# 05_-_POWER.net
KiCad netlist of a schematic drawn in Altium Designer
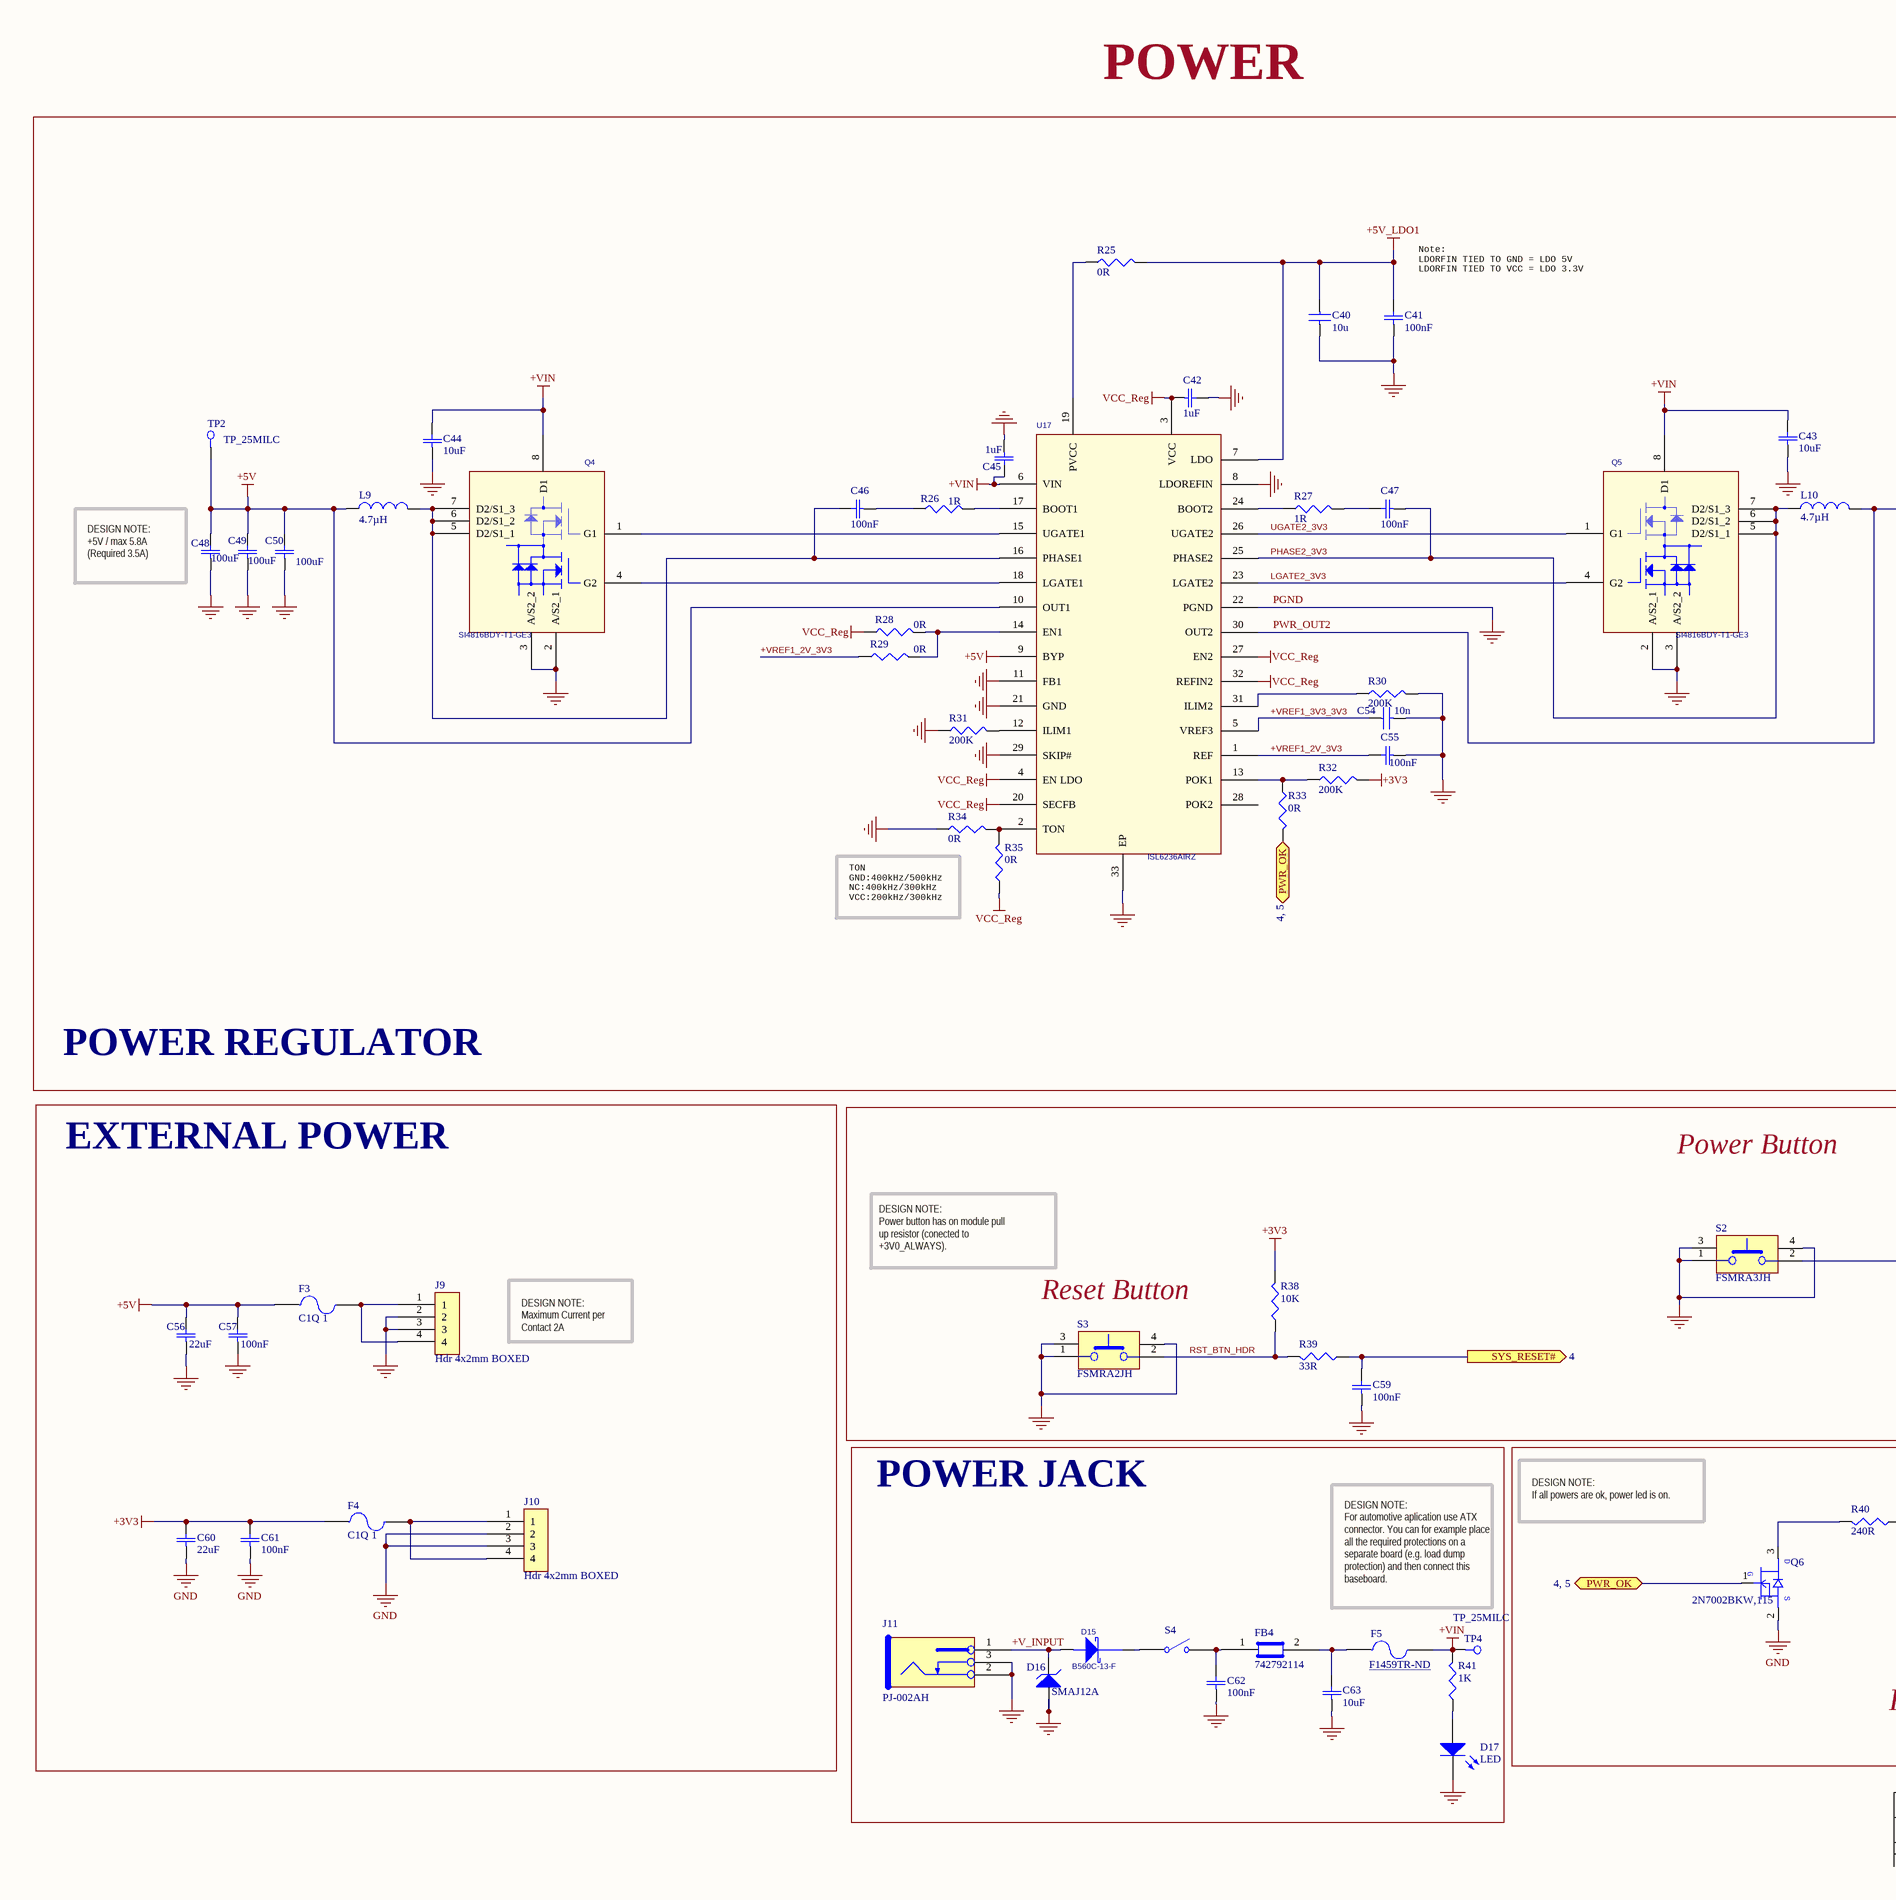
[diagram p0: [05] - POWER.SchDoc, left]
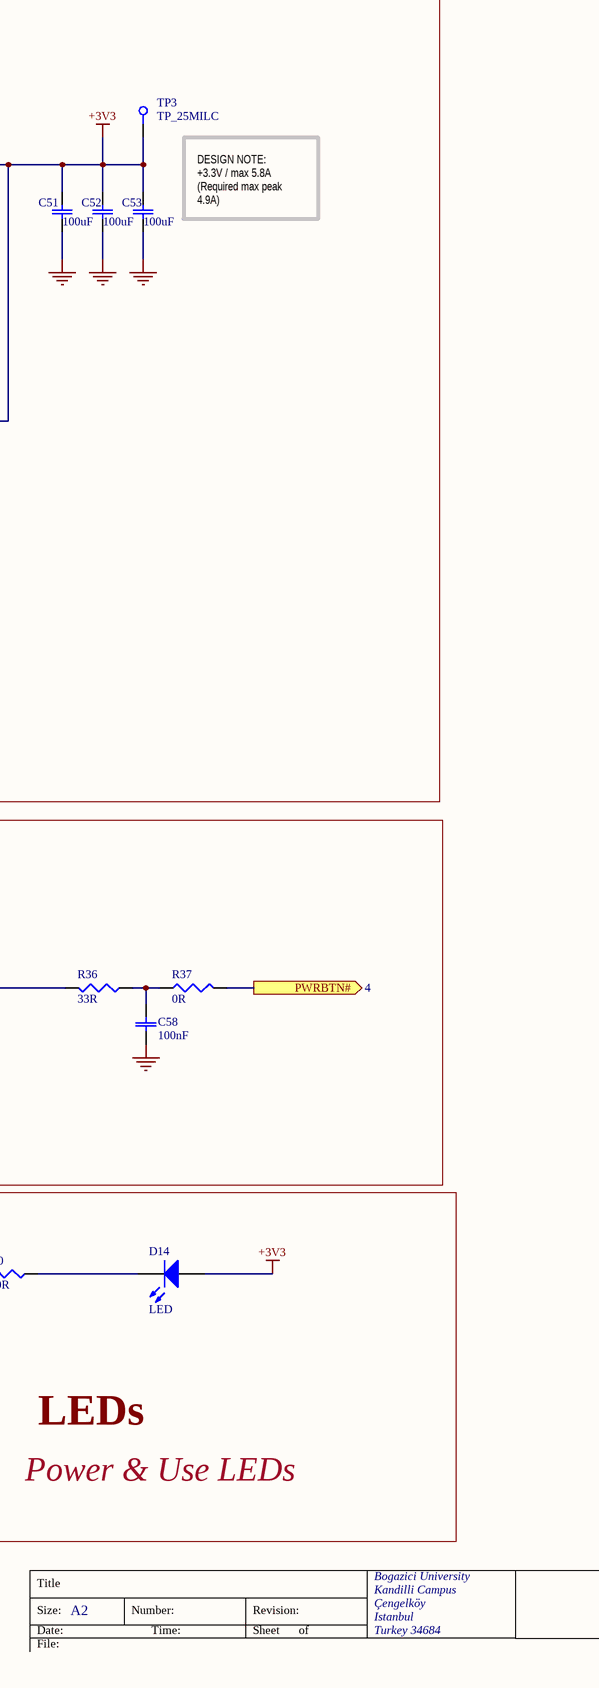
[diagram p1: [05] - POWER.SchDoc, right]

(export (version "E")
  (design (tool "Eeschema 10.0.6"))
  (components
    (comp (ref "C40")
      (value "10u")
      (footprint "iMX6 Rex Development Baseboard V1I1_PCB:C0603")
      (description "CAP CER 10UF 6.3V X5R 20% 0603")
      (fields
        (field (name "MANUFACTURER") "TDK Corporation")
        (field (name "MANUFACTURER PART NUMBER") "C1608X5R0J106M")
      )
      (libsource (lib "SYNCBOX_V3I1") (part "C1608X5R0J106M"))
    )
    (comp (ref "C41")
      (value "100nF")
      (footprint "C0402")
      (description "CAP CER 0.1UF 50V X8R 0603")
      (fields (field (name "TOLERANCE") "±10%"))
      (libsource (lib "SYNCBOX_V3I1") (part "CL05A104KA5NNNC"))
    )
    (comp (ref "C42")
      (value "1uF")
      (footprint "CAP_3216")
      (description "CAP CER 1UF 50V X8R 1206")
      (fields
        (field (name "MANUFACTURER_PART_NUMBER") "CGA5L3X8R1H105K160AB")
        (field (name "TOLERANCE") "±10%")
      )
      (libsource (lib "SYNCBOX_V3I1") (part "CGA5L3X8R1H105K1"))
    )
    (comp (ref "C43")
      (value "10uF")
      (footprint "CAP_3216")
      (description "CAP CER 10UF 35V JB 1206")
      (fields
        (field (name "TOLERANCE") "±10%")
        (field (name "MANUFACTURER_PART_NUMBER") "C3216JB1V106K160AB")
      )
      (libsource (lib "SYNCBOX_V3I1") (part "C3216JB1V106K160"))
    )
    (comp (ref "C44")
      (value "10uF")
      (footprint "CAP_3216")
      (description "CAP CER 10UF 35V JB 1206")
      (fields
        (field (name "TOLERANCE") "±10%")
        (field (name "MANUFACTURER_PART_NUMBER") "C3216JB1V106K160AB")
      )
      (libsource (lib "SYNCBOX_V3I1") (part "C3216JB1V106K160"))
    )
    (comp (ref "C45")
      (value "1uF")
      (footprint "CAP_3216")
      (description "CAP CER 1UF 50V X8R 1206")
      (fields
        (field (name "TOLERANCE") "±10%")
        (field (name "MANUFACTURER_PART_NUMBER") "CGA5L3X8R1H105K160AB")
      )
      (libsource (lib "SYNCBOX_V3I1") (part "CGA5L3X8R1H105K1"))
    )
    (comp (ref "C46")
      (value "100nF")
      (footprint "C0402")
      (description "CAP CER 0.1UF 50V X8R 0603")
      (fields (field (name "TOLERANCE") "±10%"))
      (libsource (lib "SYNCBOX_V3I1") (part "CL05A104KA5NNNC"))
    )
    (comp (ref "C47")
      (value "100nF")
      (footprint "C0402")
      (description "CAP CER 0.1UF 50V X8R 0603")
      (fields (field (name "TOLERANCE") "±10%"))
      (libsource (lib "SYNCBOX_V3I1") (part "CL05A104KA5NNNC"))
    )
    (comp (ref "C48")
      (value "100uF")
      (footprint "C1210C")
      (description "CAP CER 100UF 10V X5R 1210")
      (fields (field (name "TOLERANCE") "±20%") (field (name "MANUFACTURER_PART_NUMBER") "C1210C107M8PACTU"))
      (libsource (lib "SYNCBOX_V3I1") (part "CL32A107MPVNNNE"))
    )
    (comp (ref "C49")
      (value "100uF")
      (footprint "C1210C")
      (description "CAP CER 100UF 10V X5R 1210")
      (fields (field (name "TOLERANCE") "±20%") (field (name "MANUFACTURER_PART_NUMBER") "C1210C107M8PACTU"))
      (libsource (lib "SYNCBOX_V3I1") (part "CL32A107MPVNNNE"))
    )
    (comp (ref "C50")
      (value "100uF")
      (footprint "C1210C")
      (description "CAP CER 100UF 10V X5R 1210")
      (fields (field (name "TOLERANCE") "±20%") (field (name "MANUFACTURER_PART_NUMBER") "C1210C107M8PACTU"))
      (libsource (lib "SYNCBOX_V3I1") (part "CL32A107MPVNNNE"))
    )
    (comp (ref "C51")
      (value "100uF")
      (footprint "C1210C")
      (description "CAP CER 100UF 10V X5R 1210")
      (fields (field (name "TOLERANCE") "±20%") (field (name "MANUFACTURER_PART_NUMBER") "C1210C107M8PACTU"))
      (libsource (lib "SYNCBOX_V3I1") (part "CL32A107MPVNNNE"))
    )
    (comp (ref "C52")
      (value "100uF")
      (footprint "C1210C")
      (description "CAP CER 100UF 10V X5R 1210")
      (fields (field (name "TOLERANCE") "±20%") (field (name "MANUFACTURER_PART_NUMBER") "C1210C107M8PACTU"))
      (libsource (lib "SYNCBOX_V3I1") (part "CL32A107MPVNNNE"))
    )
    (comp (ref "C53")
      (value "100uF")
      (footprint "C1210C")
      (description "CAP CER 100UF 10V X5R 1210")
      (fields (field (name "TOLERANCE") "±20%") (field (name "MANUFACTURER_PART_NUMBER") "C1210C107M8PACTU"))
      (libsource (lib "SYNCBOX_V3I1") (part "CL32A107MPVNNNE"))
    )
    (comp (ref "C54")
      (value "10n")
      (footprint "C0402")
      (description "CAP CER 10000PF 16V X7R 10% 0402")
      (fields
        (field (name "MANUFACTURER") "TDK Corporation")
        (field (name "MANUFACTURER PART NUMBER") "C1005X7R1C103K")
      )
      (libsource (lib "SYNCBOX_V3I1") (part "C1005X7R1C103K"))
    )
    (comp (ref "C55")
      (value "100nF")
      (footprint "C0402")
      (description "CAP CER 0.1UF 50V X8R 0603")
      (fields (field (name "TOLERANCE") "±10%"))
      (libsource (lib "SYNCBOX_V3I1") (part "CL05A104KA5NNNC"))
    )
    (comp (ref "C56")
      (value "22uF")
      (footprint "C0805")
      (description "CAP CER 22UF 16V X5R 0805")
      (fields (field (name "TOLERANCE") "±20%"))
      (libsource (lib "SYNCBOX_V3I1") (part "CL21A226MOCLRNC"))
    )
    (comp (ref "C57")
      (value "100nF")
      (footprint "C0402")
      (description "CAP CER 0.1UF 50V X8R 0603")
      (fields (field (name "TOLERANCE") "±10%"))
      (libsource (lib "SYNCBOX_V3I1") (part "CL05A104KA5NNNC"))
    )
    (comp (ref "C58")
      (value "100nF")
      (footprint "C0402")
      (description "CAP CER 0.1UF 50V X8R 0603")
      (fields (field (name "TOLERANCE") "±10%"))
      (libsource (lib "SYNCBOX_V3I1") (part "CL05A104KA5NNNC"))
    )
    (comp (ref "C59")
      (value "100nF")
      (footprint "C0402")
      (description "CAP CER 0.1UF 50V X8R 0603")
      (fields (field (name "TOLERANCE") "±10%"))
      (libsource (lib "SYNCBOX_V3I1") (part "CL05A104KA5NNNC"))
    )
    (comp (ref "C60")
      (value "22uF")
      (footprint "C0805")
      (description "CAP CER 22UF 16V X5R 0805")
      (fields (field (name "TOLERANCE") "±20%"))
      (libsource (lib "SYNCBOX_V3I1") (part "CL21A226MOCLRNC"))
    )
    (comp (ref "C61")
      (value "100nF")
      (footprint "C0402")
      (description "CAP CER 0.1UF 50V X8R 0603")
      (fields (field (name "TOLERANCE") "±10%"))
      (libsource (lib "SYNCBOX_V3I1") (part "CL05A104KA5NNNC"))
    )
    (comp (ref "C62")
      (value "100nF")
      (footprint "C0402")
      (description "CAP CER 0.1UF 50V X8R 0603")
      (fields (field (name "TOLERANCE") "±10%"))
      (libsource (lib "SYNCBOX_V3I1") (part "CL05A104KA5NNNC"))
    )
    (comp (ref "C63")
      (value "10uF")
      (footprint "CAP_3216")
      (description "CAP CER 10UF 35V JB 1206")
      (fields
        (field (name "TOLERANCE") "±10%")
        (field (name "MANUFACTURER_PART_NUMBER") "C3216JB1V106K160AB")
      )
      (libsource (lib "SYNCBOX_V3I1") (part "C3216JB1V106K160"))
    )
    (comp (ref "D14")
      (value "LED")
      (footprint "D0603_Directional")
      (description "LED COOL WHITE DIFFUSED 0603 SMD")
      (libsource (lib "SYNCBOX_V3I1") (part "LW Q38E-Q1OO-3K6L-1"))
    )
    (comp (ref "D15")
      (value "B560C-13-F")
      (footprint "SYNCBOX_V3I1:SMC")
      (description "DIODE SCHOTTKY 60V 5A SMC")
      (fields (field (name "MANUFACTURER") "Diodes Inc"))
      (libsource (lib "SYNCBOX_V3I1") (part "B560C-13-F"))
    )
    (comp (ref "D16")
      (value "SMAJ12A")
      (footprint "SMA / DO-214AC")
      (description "TVS DIODE 12V 19.9V SMA")
      (fields (field (name "PUBLISHER") "Altium Limited"))
      (libsource (lib "SYNCBOX_V3I1") (part "SMAJ12A"))
    )
    (comp (ref "D17")
      (value "LED")
      (footprint "D0603_Directional")
      (description "LED COOL WHITE DIFFUSED 0603 SMD")
      (libsource (lib "SYNCBOX_V3I1") (part "LW Q38E-Q1OO-3K6L-1"))
    )
    (comp (ref "F3")
      (value "C1Q 1")
      (footprint "C1")
      (description "FUSE BOARD MOUNT 1A 125VAC 63VDC")
      (libsource (lib "SYNCBOX_V3I1") (part "C1Q 1"))
    )
    (comp (ref "F4")
      (value "C1Q 1")
      (footprint "C1")
      (description "FUSE BOARD MOUNT 1A 125VAC 63VDC")
      (libsource (lib "SYNCBOX_V3I1") (part "C1Q 1"))
    )
    (comp (ref "F5")
      (value "F1459TR-ND")
      (footprint "0466Series")
      (description "FUSE BOARD MNT 4A 32VAC/VDC 1206")
      (libsource (lib "SYNCBOX_V3I1") (part "0466004.NR"))
    )
    (comp (ref "FB4")
      (value "742792114")
      (footprint "Ferrite bead")
      (description "FERRITE BEAD 50 OHM 1206 1LN")
      (libsource (lib "SYNCBOX_V3I1") (part "FB742792114"))
    )
    (comp (ref "J9")
      (value "Hdr 4x2mm BOXED")
      (footprint "HDR_1x4_2MM_SHDR")
      (description "CONN HEADER 4POS 2MM VERT TIN")
      (fields
        (field (name "MANUFACTURER") "Molex Inc")
        (field (name "MANUFACTURER PART NUMBER") "0532530470")
        (field (name ".CREATOR") "MM")
      )
      (libsource (lib "SYNCBOX_V3I1") (part "0532530470"))
    )
    (comp (ref "J10")
      (value "Hdr 4x2mm BOXED")
      (footprint "HDR_1x4_2MM_SHDR")
      (description "CONN HEADER 4POS 2MM VERT TIN")
      (fields
        (field (name "MANUFACTURER") "Molex Inc")
        (field (name "MANUFACTURER PART NUMBER") "0532530470")
        (field (name ".CREATOR") "MM")
      )
      (libsource (lib "SYNCBOX_V3I1") (part "0532530470"))
    )
    (comp (ref "J11")
      (value "PJ-002AH")
      (footprint "POWER_JACK_5.5_2.1MM_NS")
      (description "CONN PWR JACK 2.1X5.5MM HIGH CUR")
      (fields (field (name "MANUFACTURER") "CUI Inc"))
      (libsource (lib "SYNCBOX_V3I1") (part "PJ-002AH"))
    )
    (comp (ref "L9")
      (value "4.7µH")
      (footprint "IHLP_255MILx270MIL")
      (description "INDUCTOR POWER 4.7UH 5.5A SMD")
      (fields
        (field (name "MANUFACTURER") "Vishay/Dale")
        (field (name "MANUFACTURER PART NUMBER") "IHLP2525CZER4R7M01")
      )
      (libsource (lib "SYNCBOX_V3I1") (part "IHLP2525CZER4R7M01"))
    )
    (comp (ref "L10")
      (value "4.7µH")
      (footprint "IHLP_255MILx270MIL")
      (description "INDUCTOR POWER 4.7UH 5.5A SMD")
      (fields
        (field (name "MANUFACTURER") "Vishay/Dale")
        (field (name "MANUFACTURER PART NUMBER") "IHLP2525CZER4R7M01")
      )
      (libsource (lib "SYNCBOX_V3I1") (part "IHLP2525CZER4R7M01"))
    )
    (comp (ref "Q4")
      (value "SI4816BDY-T1-GE3")
      (footprint "8_SOIC_3.9MM")
      (description "MOSFET DL N-CH 30V 6.8A 8-SOIC")
      (fields (field (name "MANUFACTURER") "Vishay/Siliconix"))
      (libsource (lib "SYNCBOX_V3I1") (part "SI4816BDY-T1-GE3"))
    )
    (comp (ref "Q5")
      (value "SI4816BDY-T1-GE3")
      (footprint "8_SOIC_3.9MM")
      (description "MOSFET DL N-CH 30V 6.8A 8-SOIC")
      (fields (field (name "MANUFACTURER") "Vishay/Siliconix"))
      (libsource (lib "SYNCBOX_V3I1") (part "SI4816BDY-T1-GE3"))
    )
    (comp (ref "Q6")
      (value "2N7002BKW,115")
      (footprint "SC70_SOT323")
      (description "MOSFET N-CH 60V 310MA SOT323")
      (fields (field (name "MANUFACTURER") "NXP Semiconductors"))
      (libsource (lib "SYNCBOX_V3I1") (part "2N7002BKW,115"))
    )
    (comp (ref "R25")
      (value "0R")
      (footprint "R0402")
      (description "RES SMD 0 OHM JUMPER 1/16W 0402")
      (fields (field (name "TOLERANCE") "Jumper"))
      (libsource (lib "SYNCBOX_V3I1") (part "RC1005J000CS"))
    )
    (comp (ref "R26")
      (value "1R")
      (footprint "R0402")
      (description "RES 1.00 OHM 1/16W 1% 0402 SM")
      (fields
        (field (name "MANUFACTURER") "Yageo")
        (field (name "MANUFACTURER PART NUMBER") "RC0402FR-071RL")
      )
      (libsource (lib "SYNCBOX_V3I1") (part "RC0402FR-071RL"))
    )
    (comp (ref "R27")
      (value "1R")
      (footprint "R0402")
      (description "RES 1.00 OHM 1/16W 1% 0402 SM")
      (fields
        (field (name "MANUFACTURER") "Yageo")
        (field (name "MANUFACTURER PART NUMBER") "RC0402FR-071RL")
      )
      (libsource (lib "SYNCBOX_V3I1") (part "RC0402FR-071RL"))
    )
    (comp (ref "R28")
      (value "0R")
      (footprint "R0402")
      (description "RES SMD 0 OHM JUMPER 1/16W 0402")
      (fields (field (name "TOLERANCE") "Jumper"))
      (libsource (lib "SYNCBOX_V3I1") (part "RC1005J000CS"))
    )
    (comp (ref "R29")
      (value "0R")
      (footprint "R0402")
      (description "RES SMD 0 OHM JUMPER 1/16W 0402")
      (fields (field (name "TOLERANCE") "Jumper"))
      (libsource (lib "SYNCBOX_V3I1") (part "RC1005J000CS"))
    )
    (comp (ref "R30")
      (value "200K")
      (footprint "R0402")
      (description "RES SMD 200K OHM 1% 1/16W 0402")
      (fields (field (name "TOLERANCE") "±1%"))
      (libsource (lib "SYNCBOX_V3I1") (part "RC1005F204CS"))
    )
    (comp (ref "R31")
      (value "200K")
      (footprint "R0402")
      (description "RES SMD 200K OHM 1% 1/16W 0402")
      (fields (field (name "TOLERANCE") "±1%"))
      (libsource (lib "SYNCBOX_V3I1") (part "RC1005F204CS"))
    )
    (comp (ref "R32")
      (value "200K")
      (footprint "R0402")
      (description "RES SMD 200K OHM 1% 1/16W 0402")
      (fields (field (name "TOLERANCE") "±1%"))
      (libsource (lib "SYNCBOX_V3I1") (part "RC1005F204CS"))
    )
    (comp (ref "R33")
      (value "0R")
      (footprint "R0402")
      (description "RES SMD 0 OHM JUMPER 1/16W 0402")
      (fields (field (name "TOLERANCE") "Jumper"))
      (libsource (lib "SYNCBOX_V3I1") (part "RC1005J000CS"))
    )
    (comp (ref "R34")
      (value "0R")
      (footprint "R0402")
      (description "RES SMD 0 OHM JUMPER 1/16W 0402")
      (fields (field (name "TOLERANCE") "Jumper"))
      (libsource (lib "SYNCBOX_V3I1") (part "RC1005J000CS"))
    )
    (comp (ref "R35")
      (value "0R")
      (footprint "R0402")
      (description "RES SMD 0 OHM JUMPER 1/16W 0402")
      (fields (field (name "TOLERANCE") "Jumper"))
      (libsource (lib "SYNCBOX_V3I1") (part "RC1005J000CS"))
    )
    (comp (ref "R36")
      (value "33R")
      (footprint "R0402")
      (description "RES SMD 33 OHM 1% 1/10W 0402")
      (fields (field (name "TOLERANCE") "±1%"))
      (libsource (lib "SYNCBOX_V3I1") (part "ERJ-2RKF33R0X"))
    )
    (comp (ref "R37")
      (value "0R")
      (footprint "R0402")
      (description "RES SMD 0 OHM JUMPER 1/16W 0402")
      (fields (field (name "TOLERANCE") "Jumper"))
      (libsource (lib "SYNCBOX_V3I1") (part "RC1005J000CS"))
    )
    (comp (ref "R38")
      (value "10K")
      (footprint "R0402")
      (description "RES SMD 10K OHM 1% 1/16W 0402")
      (fields (field (name "TOLERANCE") "±1%"))
      (libsource (lib "SYNCBOX_V3I1") (part "RC1005F103CS"))
    )
    (comp (ref "R39")
      (value "33R")
      (footprint "R0402")
      (description "RES SMD 33 OHM 1% 1/10W 0402")
      (fields (field (name "TOLERANCE") "±1%"))
      (libsource (lib "SYNCBOX_V3I1") (part "ERJ-2RKF33R0X"))
    )
    (comp (ref "R40")
      (value "240R")
      (footprint "R0402")
      (description "RES TF 240 OHM 1% 0.0625W 0402")
      (fields
        (field (name "MANUFACTURER") "Stackpole Electronics Inc")
        (field (name "MANUFACTURER PART NUMBER") "RMCF0402FT240R")
      )
      (libsource (lib "SYNCBOX_V3I1") (part "RMCF0402FT240R"))
    )
    (comp (ref "R41")
      (value "1K")
      (footprint "R0402")
      (description "RES SMD 1K OHM 1% 1/10W 0402")
      (fields (field (name "TOLERANCE") "±1%"))
      (libsource (lib "SYNCBOX_V3I1") (part "ERJ-2RKF1001X"))
    )
    (comp (ref "S2")
      (value "FSMRA3JH")
      (footprint "iMX6 Rex Development Baseboard V1I1_PCB:FSMRA3JH")
      (description "SWITCH TACTILE SPST-NO 0.05A 12V")
      (fields (field (name "MANUFACTURER") "TE Connectivity") (field (name ".CREATOR") "MM"))
      (libsource (lib "SYNCBOX_V3I1") (part "FSMRA3JH"))
    )
    (comp (ref "S3")
      (value "FSMRA2JH")
      (footprint "FSMRA2JH")
      (description "SWITCH TACTILE SPST-NO 0.05A 24V")
      (libsource (lib "SYNCBOX_V3I1") (part "FSMRA2JH"))
    )
    (comp (ref "S4")
      (value "R1966ABLKBLKGR")
      (footprint "RockerSwitch")
      (description "SWITCH ROCKER SPST 15A 125V")
      (fields (field (name "PUBLISHER") "Altium Limited"))
      (libsource (lib "SYNCBOX_V3I1") (part "R1966ABLKBLKGR"))
    )
    (comp (ref "TP2")
      (value "TP_25MILC")
      (footprint "TP_25C")
      (description "Test Point 25mil")
      (libsource (lib "SYNCBOX_V3I1") (part "TP_25MILC"))
    )
    (comp (ref "TP3")
      (value "TP_25MILC")
      (footprint "TP_25C")
      (description "Test Point 25mil")
      (libsource (lib "SYNCBOX_V3I1") (part "TP_25MILC"))
    )
    (comp (ref "TP4")
      (value "TP_25MILC")
      (footprint "TP_25C")
      (description "Test Point 25mil")
      (libsource (lib "SYNCBOX_V3I1") (part "TP_25MILC"))
    )
    (comp (ref "U17")
      (value "ISL6236AIRZ")
      (footprint "iMX6 Rex Development Baseboard V1I1_PCB:32_VFQFN_EXPOSED_PAD")
      (description "IC MAIN PWR CTRLR QUAD 32-QFN")
      (fields (field (name "MANUFACTURER") "Intersil"))
      (libsource (lib "SYNCBOX_V3I1") (part "ISL6236AIRZ"))
    )
  )
  (nets
    (net (code "1") (name "+3V3") (class "Default")
      (node (ref "C51") (pin "2") (pinfunction "2_2") (pintype "passive"))
      (node (ref "C52") (pin "2") (pinfunction "2_2") (pintype "passive"))
      (node (ref "C53") (pin "2") (pinfunction "2_2") (pintype "passive"))
      (node (ref "C60") (pin "2") (pinfunction "2_2") (pintype "passive"))
      (node (ref "C61") (pin "2") (pinfunction "2_2") (pintype "passive"))
      (node (ref "D14") (pin "1") (pinfunction "A_1") (pintype "passive"))
      (node (ref "F4") (pin "1") (pinfunction "1_1") (pintype "passive"))
      (node (ref "L10") (pin "2") (pinfunction "2_2") (pintype "passive"))
      (node (ref "R32") (pin "2") (pinfunction "2_2") (pintype "passive"))
      (node (ref "R38") (pin "2") (pinfunction "2_2") (pintype "passive"))
      (node (ref "TP3") (pin "1") (pinfunction "1_1") (pintype "passive"))
      (node (ref "U17") (pin "30") (pinfunction "OUT2_30") (pintype "passive"))
    )
    (net (code "2") (name "+5V") (class "Default")
      (node (ref "C48") (pin "2") (pinfunction "2_2") (pintype "passive"))
      (node (ref "C49") (pin "2") (pinfunction "2_2") (pintype "passive"))
      (node (ref "C50") (pin "2") (pinfunction "2_2") (pintype "passive"))
      (node (ref "C56") (pin "2") (pinfunction "2_2") (pintype "passive"))
      (node (ref "C57") (pin "2") (pinfunction "2_2") (pintype "passive"))
      (node (ref "F3") (pin "1") (pinfunction "1_1") (pintype "passive"))
      (node (ref "L9") (pin "1") (pinfunction "1_1") (pintype "passive"))
      (node (ref "TP2") (pin "1") (pinfunction "1_1") (pintype "passive"))
      (node (ref "U17") (pin "10") (pinfunction "OUT1_10") (pintype "passive"))
      (node (ref "U17") (pin "9") (pinfunction "BYP_9") (pintype "passive"))
    )
    (net (code "3") (name "+5V_LDO1") (class "Default")
      (node (ref "C40") (pin "1") (pinfunction "1_1") (pintype "passive"))
      (node (ref "C41") (pin "2") (pinfunction "2_2") (pintype "passive"))
      (node (ref "R25") (pin "2") (pinfunction "2_2") (pintype "passive"))
      (node (ref "U17") (pin "7") (pinfunction "LDO_7") (pintype "passive"))
    )
    (net (code "4") (name "+VIN") (class "Default")
      (node (ref "C43") (pin "2") (pinfunction "2_2") (pintype "passive"))
      (node (ref "C44") (pin "2") (pinfunction "2_2") (pintype "passive"))
      (node (ref "C45") (pin "2") (pinfunction "2_2") (pintype "passive"))
      (node (ref "F5") (pin "2") (pinfunction "2_2") (pintype "passive"))
      (node (ref "Q4") (pin "8") (pinfunction "D1_8") (pintype "passive"))
      (node (ref "Q5") (pin "8") (pinfunction "D1_8") (pintype "passive"))
      (node (ref "R41") (pin "2") (pinfunction "2_2") (pintype "passive"))
      (node (ref "TP4") (pin "1") (pinfunction "1_1") (pintype "passive"))
      (node (ref "U17") (pin "6") (pinfunction "VIN_6") (pintype "passive"))
    )
    (net (code "5") (name "/+VREF1_2V_3V3") (class "Default")
      (node (ref "C55") (pin "2") (pinfunction "2_2") (pintype "passive"))
      (node (ref "R29") (pin "1") (pinfunction "1_1") (pintype "passive"))
      (node (ref "U17") (pin "1") (pinfunction "REF_1") (pintype "passive"))
    )
    (net (code "6") (name "/+VREF1_3V3_3V3") (class "Default")
      (node (ref "C54") (pin "1") (pinfunction "1_1") (pintype "passive"))
      (node (ref "U17") (pin "5") (pinfunction "VREF3_5") (pintype "passive"))
    )
    (net (code "7") (name "/+V_INPUT") (class "Default")
      (node (ref "D15") (pin "2") (pinfunction "ANODE_2") (pintype "passive"))
      (node (ref "D16") (pin "2") (pinfunction "K_2") (pintype "passive"))
      (node (ref "J11") (pin "1") (pinfunction "1_1") (pintype "passive"))
    )
    (net (code "8") (name "/LGATE2_3V3") (class "Default")
      (node (ref "Q5") (pin "4") (pinfunction "G2_4") (pintype "passive"))
      (node (ref "U17") (pin "23") (pinfunction "LGATE2_23") (pintype "passive"))
    )
    (net (code "9") (name "/PHASE2_3V3") (class "Default")
      (node (ref "C47") (pin "1") (pinfunction "1_1") (pintype "passive"))
      (node (ref "L10") (pin "1") (pinfunction "1_1") (pintype "passive"))
      (node (ref "Q5") (pin "5") (pinfunction "D2/S1_1_5") (pintype "passive"))
      (node (ref "Q5") (pin "6") (pinfunction "D2/S1_2_6") (pintype "passive"))
      (node (ref "Q5") (pin "7") (pinfunction "D2/S1_3_7") (pintype "passive"))
      (node (ref "U17") (pin "25") (pinfunction "PHASE2_25") (pintype "passive"))
    )
    (net (code "10") (name "/PWRBTN#") (class "Default")
      (node (ref "R37") (pin "2") (pinfunction "2_2") (pintype "passive"))
    )
    (net (code "11") (name "/PWR_OK") (class "Default")
      (node (ref "Q6") (pin "1") (pinfunction "GATE_1") (pintype "passive"))
      (node (ref "R33") (pin "2") (pinfunction "2_2") (pintype "passive"))
    )
    (net (code "12") (name "/RST_BTN_HDR") (class "Default")
      (node (ref "R38") (pin "1") (pinfunction "1_1") (pintype "passive"))
      (node (ref "R39") (pin "2") (pinfunction "2_2") (pintype "passive"))
      (node (ref "S3") (pin "2") (pinfunction "2_2") (pintype "passive"))
    )
    (net (code "13") (name "/SYS_RESET#") (class "Default")
      (node (ref "C59") (pin "2") (pinfunction "2_2") (pintype "passive"))
      (node (ref "R39") (pin "1") (pinfunction "1_1") (pintype "passive"))
    )
    (net (code "14") (name "/UGATE2_3V3") (class "Default")
      (node (ref "Q5") (pin "1") (pinfunction "G1_1") (pintype "passive"))
      (node (ref "U17") (pin "26") (pinfunction "UGATE2_26") (pintype "passive"))
    )
    (net (code "15") (name "GND") (class "Default")
      (node (ref "C40") (pin "2") (pinfunction "2_2") (pintype "passive"))
      (node (ref "C41") (pin "1") (pinfunction "1_1") (pintype "passive"))
      (node (ref "C42") (pin "2") (pinfunction "2_2") (pintype "passive"))
      (node (ref "C43") (pin "1") (pinfunction "1_1") (pintype "passive"))
      (node (ref "C44") (pin "1") (pinfunction "1_1") (pintype "passive"))
      (node (ref "C45") (pin "1") (pinfunction "1_1") (pintype "passive"))
      (node (ref "C48") (pin "1") (pinfunction "1_1") (pintype "passive"))
      (node (ref "C49") (pin "1") (pinfunction "1_1") (pintype "passive"))
      (node (ref "C50") (pin "1") (pinfunction "1_1") (pintype "passive"))
      (node (ref "C51") (pin "1") (pinfunction "1_1") (pintype "passive"))
      (node (ref "C52") (pin "1") (pinfunction "1_1") (pintype "passive"))
      (node (ref "C53") (pin "1") (pinfunction "1_1") (pintype "passive"))
      (node (ref "C54") (pin "2") (pinfunction "2_2") (pintype "passive"))
      (node (ref "C55") (pin "1") (pinfunction "1_1") (pintype "passive"))
      (node (ref "C56") (pin "1") (pinfunction "1_1") (pintype "passive"))
      (node (ref "C57") (pin "1") (pinfunction "1_1") (pintype "passive"))
      (node (ref "C58") (pin "1") (pinfunction "1_1") (pintype "passive"))
      (node (ref "C59") (pin "1") (pinfunction "1_1") (pintype "passive"))
      (node (ref "C60") (pin "1") (pinfunction "1_1") (pintype "passive"))
      (node (ref "C61") (pin "1") (pinfunction "1_1") (pintype "passive"))
      (node (ref "C62") (pin "1") (pinfunction "1_1") (pintype "passive"))
      (node (ref "C63") (pin "1") (pinfunction "1_1") (pintype "passive"))
      (node (ref "D16") (pin "1") (pinfunction "A_1") (pintype "passive"))
      (node (ref "D17") (pin "2") (pinfunction "K_2") (pintype "passive"))
      (node (ref "J10") (pin "2") (pinfunction "2_2") (pintype "passive"))
      (node (ref "J10") (pin "3") (pinfunction "3_3") (pintype "passive"))
      (node (ref "J11") (pin "2") (pinfunction "2_2") (pintype "passive"))
      (node (ref "J11") (pin "3") (pinfunction "3_3") (pintype "passive"))
      (node (ref "J9") (pin "2") (pinfunction "2_2") (pintype "passive"))
      (node (ref "J9") (pin "3") (pinfunction "3_3") (pintype "passive"))
      (node (ref "Q4") (pin "2") (pinfunction "A/S2_1_2") (pintype "passive"))
      (node (ref "Q4") (pin "3") (pinfunction "A/S2_2_3") (pintype "passive"))
      (node (ref "Q5") (pin "2") (pinfunction "A/S2_1_2") (pintype "passive"))
      (node (ref "Q5") (pin "3") (pinfunction "A/S2_2_3") (pintype "passive"))
      (node (ref "Q6") (pin "2") (pinfunction "SOURCE_2") (pintype "passive"))
      (node (ref "R30") (pin "2") (pinfunction "2_2") (pintype "passive"))
      (node (ref "R31") (pin "1") (pinfunction "1_1") (pintype "passive"))
      (node (ref "R34") (pin "1") (pinfunction "1_1") (pintype "passive"))
      (node (ref "S2") (pin "1") (pinfunction "1_1") (pintype "passive"))
      (node (ref "S2") (pin "3") (pinfunction "MECH1_3") (pintype "passive"))
      (node (ref "S2") (pin "4") (pinfunction "MECH2_4") (pintype "passive"))
      (node (ref "S3") (pin "1") (pinfunction "1_1") (pintype "passive"))
      (node (ref "S3") (pin "3") (pinfunction "MECH1_3") (pintype "passive"))
      (node (ref "S3") (pin "4") (pinfunction "MECH2_4") (pintype "passive"))
      (node (ref "U17") (pin "11") (pinfunction "FB1_11") (pintype "passive"))
      (node (ref "U17") (pin "21") (pinfunction "GND_21") (pintype "passive"))
      (node (ref "U17") (pin "22") (pinfunction "PGND_22") (pintype "passive"))
      (node (ref "U17") (pin "29") (pinfunction "SKIP#_29") (pintype "passive"))
      (node (ref "U17") (pin "33") (pinfunction "EP_33") (pintype "passive"))
      (node (ref "U17") (pin "8") (pinfunction "LDOREFIN_8") (pintype "passive"))
    )
    (net (code "16") (name "Net-(C46-Pad1)") (class "Default")
      (node (ref "C46") (pin "1") (pinfunction "1_1") (pintype "passive"))
      (node (ref "R26") (pin "1") (pinfunction "1_1") (pintype "passive"))
    )
    (net (code "17") (name "Net-(C47-Pad2)") (class "Default")
      (node (ref "C47") (pin "2") (pinfunction "2_2") (pintype "passive"))
      (node (ref "R27") (pin "2") (pinfunction "2_2") (pintype "passive"))
    )
    (net (code "18") (name "Net-(C58-Pad2)") (class "Default")
      (node (ref "C58") (pin "2") (pinfunction "2_2") (pintype "passive"))
      (node (ref "R36") (pin "1") (pinfunction "1_1") (pintype "passive"))
      (node (ref "R37") (pin "1") (pinfunction "1_1") (pintype "passive"))
    )
    (net (code "19") (name "Net-(C63-Pad2)") (class "Default")
      (node (ref "C63") (pin "2") (pinfunction "2_2") (pintype "passive"))
      (node (ref "F5") (pin "1") (pinfunction "1_1") (pintype "passive"))
      (node (ref "FB4") (pin "2") (pinfunction "2_2") (pintype "passive"))
    )
    (net (code "20") (name "Net-(D14-K)") (class "Default")
      (node (ref "D14") (pin "2") (pinfunction "K_2") (pintype "passive"))
      (node (ref "R40") (pin "1") (pinfunction "1_1") (pintype "passive"))
    )
    (net (code "21") (name "Net-(D15-cathode)") (class "Default")
      (node (ref "D15") (pin "1") (pinfunction "cathode_1") (pintype "passive"))
      (node (ref "S4") (pin "1") (pinfunction "COMMON_1") (pintype "passive"))
    )
    (net (code "22") (name "Net-(D17-A)") (class "Default")
      (node (ref "D17") (pin "1") (pinfunction "A_1") (pintype "passive"))
      (node (ref "R41") (pin "1") (pinfunction "1_1") (pintype "passive"))
    )
    (net (code "23") (name "Net-(F3-Pad2)") (class "Default")
      (node (ref "F3") (pin "2") (pinfunction "2_2") (pintype "passive"))
      (node (ref "J9") (pin "1") (pinfunction "1_1") (pintype "passive"))
      (node (ref "J9") (pin "4") (pinfunction "4_4") (pintype "passive"))
    )
    (net (code "24") (name "Net-(F4-Pad2)") (class "Default")
      (node (ref "F4") (pin "2") (pinfunction "2_2") (pintype "passive"))
      (node (ref "J10") (pin "1") (pinfunction "1_1") (pintype "passive"))
      (node (ref "J10") (pin "4") (pinfunction "4_4") (pintype "passive"))
    )
    (net (code "25") (name "Net-(Q4-D2{slash}S1_1)") (class "Default")
      (node (ref "C46") (pin "2") (pinfunction "2_2") (pintype "passive"))
      (node (ref "L9") (pin "2") (pinfunction "2_2") (pintype "passive"))
      (node (ref "Q4") (pin "5") (pinfunction "D2/S1_1_5") (pintype "passive"))
      (node (ref "Q4") (pin "6") (pinfunction "D2/S1_2_6") (pintype "passive"))
      (node (ref "Q4") (pin "7") (pinfunction "D2/S1_3_7") (pintype "passive"))
      (node (ref "U17") (pin "16") (pinfunction "PHASE1_16") (pintype "passive"))
    )
    (net (code "26") (name "Net-(Q4-G1)") (class "Default")
      (node (ref "Q4") (pin "1") (pinfunction "G1_1") (pintype "passive"))
      (node (ref "U17") (pin "15") (pinfunction "UGATE1_15") (pintype "passive"))
    )
    (net (code "27") (name "Net-(Q4-G2)") (class "Default")
      (node (ref "Q4") (pin "4") (pinfunction "G2_4") (pintype "passive"))
      (node (ref "U17") (pin "18") (pinfunction "LGATE1_18") (pintype "passive"))
    )
    (net (code "28") (name "Net-(Q6-DRAIN)") (class "Default")
      (node (ref "Q6") (pin "3") (pinfunction "DRAIN_3") (pintype "passive"))
      (node (ref "R40") (pin "2") (pinfunction "2_2") (pintype "passive"))
    )
    (net (code "29") (name "Net-(R36-Pad2)") (class "Default")
      (node (ref "R36") (pin "2") (pinfunction "2_2") (pintype "passive"))
      (node (ref "S2") (pin "2") (pinfunction "2_2") (pintype "passive"))
    )
    (net (code "30") (name "Net-(S4-NO)") (class "Default")
      (node (ref "C62") (pin "2") (pinfunction "2_2") (pintype "passive"))
      (node (ref "FB4") (pin "1") (pinfunction "1_1") (pintype "passive"))
      (node (ref "S4") (pin "2") (pinfunction "NO_2") (pintype "passive"))
    )
    (net (code "31") (name "Net-(U17-BOOT1)") (class "Default")
      (node (ref "R26") (pin "2") (pinfunction "2_2") (pintype "passive"))
      (node (ref "U17") (pin "17") (pinfunction "BOOT1_17") (pintype "passive"))
    )
    (net (code "32") (name "Net-(U17-BOOT2)") (class "Default")
      (node (ref "R27") (pin "1") (pinfunction "1_1") (pintype "passive"))
      (node (ref "U17") (pin "24") (pinfunction "BOOT2_24") (pintype "passive"))
    )
    (net (code "33") (name "Net-(U17-EN1)") (class "Default")
      (node (ref "R28") (pin "2") (pinfunction "2_2") (pintype "passive"))
      (node (ref "R29") (pin "2") (pinfunction "2_2") (pintype "passive"))
      (node (ref "U17") (pin "14") (pinfunction "EN1_14") (pintype "passive"))
    )
    (net (code "34") (name "Net-(U17-ILIM1)") (class "Default")
      (node (ref "R31") (pin "2") (pinfunction "2_2") (pintype "passive"))
      (node (ref "U17") (pin "12") (pinfunction "ILIM1_12") (pintype "passive"))
    )
    (net (code "35") (name "Net-(U17-ILIM2)") (class "Default")
      (node (ref "R30") (pin "1") (pinfunction "1_1") (pintype "passive"))
      (node (ref "U17") (pin "31") (pinfunction "ILIM2_31") (pintype "passive"))
    )
    (net (code "36") (name "Net-(U17-POK1)") (class "Default")
      (node (ref "R32") (pin "1") (pinfunction "1_1") (pintype "passive"))
      (node (ref "R33") (pin "1") (pinfunction "1_1") (pintype "passive"))
      (node (ref "U17") (pin "13") (pinfunction "POK1_13") (pintype "passive"))
    )
    (net (code "37") (name "Net-(U17-PVCC)") (class "Default")
      (node (ref "R25") (pin "1") (pinfunction "1_1") (pintype "passive"))
      (node (ref "U17") (pin "19") (pinfunction "PVCC_19") (pintype "passive"))
    )
    (net (code "38") (name "Net-(U17-TON)") (class "Default")
      (node (ref "R34") (pin "2") (pinfunction "2_2") (pintype "passive"))
      (node (ref "R35") (pin "2") (pinfunction "2_2") (pintype "passive"))
      (node (ref "U17") (pin "2") (pinfunction "TON_2") (pintype "passive"))
    )
    (net (code "39") (name "VCC_Reg") (class "Default")
      (node (ref "C42") (pin "1") (pinfunction "1_1") (pintype "passive"))
      (node (ref "R28") (pin "1") (pinfunction "1_1") (pintype "passive"))
      (node (ref "R35") (pin "1") (pinfunction "1_1") (pintype "passive"))
      (node (ref "U17") (pin "20") (pinfunction "SECFB_20") (pintype "passive"))
      (node (ref "U17") (pin "27") (pinfunction "EN2_27") (pintype "passive"))
      (node (ref "U17") (pin "3") (pinfunction "VCC_3") (pintype "passive"))
      (node (ref "U17") (pin "32") (pinfunction "REFIN2_32") (pintype "passive"))
      (node (ref "U17") (pin "4") (pinfunction "EN_LDO_4") (pintype "passive"))
    )
    (net (code "40") (name "unconnected-(U17-POK2-Pad28)") (class "Default")
      (node (ref "U17") (pin "28") (pinfunction "POK2_28") (pintype "passive"))
    )
  )
)
